# esquemacamisetawifi.net
KiCad netlist of a schematic drawn in EAGLE
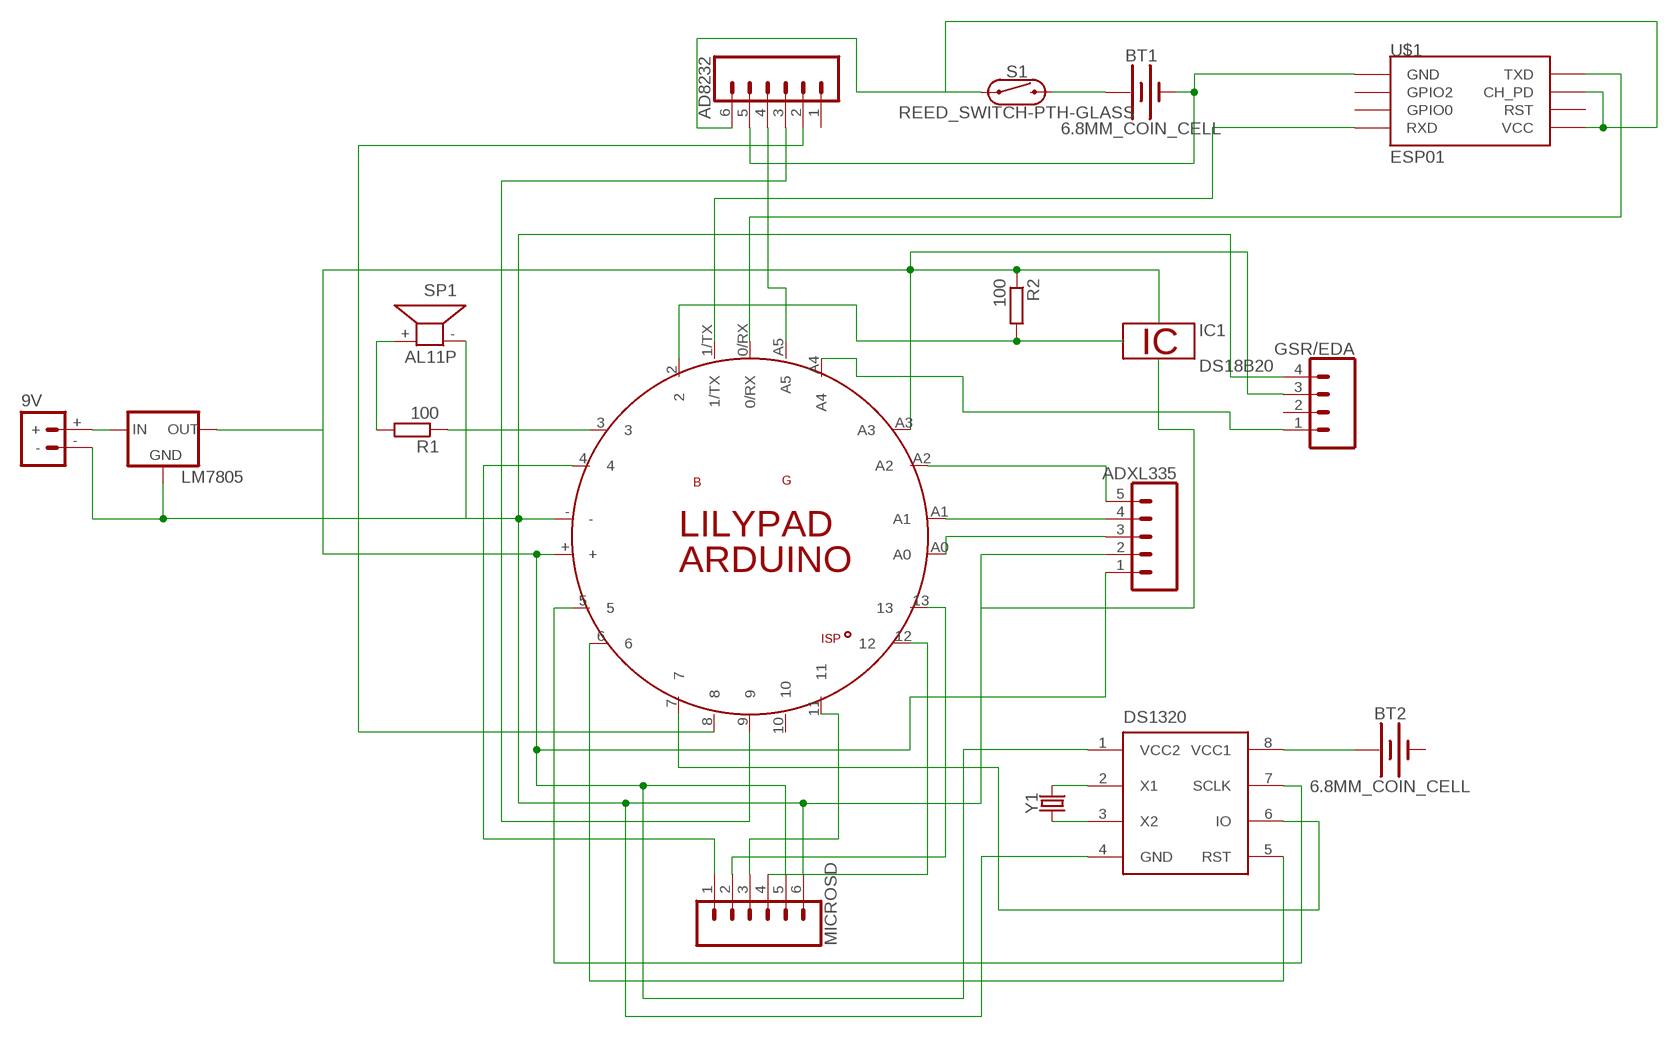
[diagram p0: schematic, sheet 1]

(export (version "E")
  (design (tool "Eeschema 10.0.6"))
  (components
    (comp (ref "9V")
      (value "BATTERY_CONN_DEANS")
      (footprint "eagle-import:DEANS")
      (libsource (lib "eagle-import") (part "BATTERY_CONN_DEANS"))
    )
    (comp (ref "AD8232")
      (value "CONN_06FEMALE_LOCK")
      (footprint "eagle-import:1X06_FEMALE_LOCK.010")
      (libsource (lib "eagle-import") (part "CONN_06FEMALE_LOCK"))
    )
    (comp (ref "ADXL335")
      (value "CONN_05")
      (footprint "eagle-import:1X05")
      (libsource (lib "eagle-import") (part "CONN_05"))
    )
    (comp (ref "BT1")
      (value "6.8MM_COIN_CELL")
      (footprint "eagle-import:BATTCON-6.8MM")
      (libsource (lib "eagle-import") (part "BATTERY-6.8MM_SMD"))
    )
    (comp (ref "BT2")
      (value "6.8MM_COIN_CELL")
      (footprint "eagle-import:BATTCON-6.8MM")
      (libsource (lib "eagle-import") (part "BATTERY-6.8MM_SMD"))
    )
    (comp (ref "DS1320")
      (value "DS1302")
      (footprint "eagle-import:PDIP8")
      (libsource (lib "eagle-import") (part "DS1302"))
    )
    (comp (ref "GSR/EDA")
      (value "CONN_04JST-PTH")
      (footprint "eagle-import:JST-4-PTH")
      (libsource (lib "eagle-import") (part "CONN_04JST-PTH"))
    )
    (comp (ref "IC1")
      (value "DS18B20")
      (footprint "eagle-import:TO92-")
      (libsource (lib "eagle-import") (part "DS18B20"))
    )
    (comp (ref "LM7805")
      (value "V_REG_78XX-TO-220")
      (footprint "eagle-import:TO-220-ALT")
      (libsource (lib "eagle-import") (part "V_REG_78XX-TO-220"))
    )
    (comp (ref "MICROSD")
      (value "CONN_06FEMALE_LOCK")
      (footprint "eagle-import:1X06_FEMALE_LOCK.010")
      (libsource (lib "eagle-import") (part "CONN_06FEMALE_LOCK"))
    )
    (comp (ref "PCB1")
      (value "ARDUINO_LILYPAD")
      (footprint "eagle-import:ARDUINO_LILYPAD")
      (libsource (lib "eagle-import") (part "ARDUINO_LILYPAD"))
    )
    (comp (ref "R1")
      (value "100")
      (footprint "eagle-import:0309_12")
      (libsource (lib "eagle-import") (part "R-EU_0309/12"))
    )
    (comp (ref "R2")
      (value "100")
      (footprint "eagle-import:0309_12")
      (libsource (lib "eagle-import") (part "R-EU_0309/12"))
    )
    (comp (ref "S1")
      (value "REED_SWITCH-PTH-GLASS")
      (footprint "eagle-import:REED_SWITCH_GLASS")
      (libsource (lib "eagle-import") (part "REED_SWITCH-PTH-GLASS"))
    )
    (comp (ref "SP1")
      (value "AL11P")
      (footprint "eagle-import:AL11P")
      (libsource (lib "eagle-import") (part "AL11P"))
    )
    (comp (ref "U$1")
      (value "ESP01")
      (footprint "eagle-import:ESP01")
      (libsource (lib "eagle-import") (part "ESP01"))
    )
    (comp (ref "Y1")
      (value "CRYSTALPTH-2X6")
      (footprint "eagle-import:CRYSTAL-PTH-2X6-CYL")
      (libsource (lib "eagle-import") (part "CRYSTALPTH-2X6"))
    )
  )
  (nets
    (net (code "1") (name "/-") (class "Default")
      (node (ref "BT2") (pin "-") (pinfunction "-_-") (pintype "power_in"))
    )
    (net (code "2") (name "Net-(9V-Pad+)") (class "Default")
      (node (ref "9V") (pin "+") (pinfunction "+_+") (pintype "passive"))
      (node (ref "LM7805") (pin "IN") (pinfunction "IN_IN") (pintype "input"))
    )
    (net (code "3") (name "Net-(AD8232-Pad2)") (class "Default")
      (node (ref "AD8232") (pin "2") (pinfunction "2_2") (pintype "passive"))
      (node (ref "PCB1") (pin "8") (pinfunction "8_8") (pintype "bidirectional"))
    )
    (net (code "4") (name "Net-(AD8232-Pad3)") (class "Default")
      (node (ref "AD8232") (pin "3") (pinfunction "3_3") (pintype "passive"))
      (node (ref "PCB1") (pin "9") (pinfunction "9_9") (pintype "bidirectional"))
    )
    (net (code "5") (name "Net-(AD8232-Pad4)") (class "Default")
      (node (ref "AD8232") (pin "4") (pinfunction "4_4") (pintype "passive"))
      (node (ref "PCB1") (pin "A5") (pinfunction "A5_A5") (pintype "bidirectional"))
    )
    (net (code "6") (name "Net-(AD8232-Pad5)") (class "Default")
      (node (ref "AD8232") (pin "5") (pinfunction "5_5") (pintype "passive"))
      (node (ref "BT1") (pin "-") (pinfunction "-_-") (pintype "power_in"))
      (node (ref "U$1") (pin "GND") (pinfunction "GND_GND") (pintype "bidirectional"))
    )
    (net (code "7") (name "Net-(ADXL335-Pad3)") (class "Default")
      (node (ref "ADXL335") (pin "3") (pinfunction "3_3") (pintype "passive"))
      (node (ref "PCB1") (pin "A0") (pinfunction "A0_A0") (pintype "bidirectional"))
    )
    (net (code "8") (name "Net-(ADXL335-Pad4)") (class "Default")
      (node (ref "ADXL335") (pin "4") (pinfunction "4_4") (pintype "passive"))
      (node (ref "PCB1") (pin "A1") (pinfunction "A1_A1") (pintype "bidirectional"))
    )
    (net (code "9") (name "Net-(ADXL335-Pad5)") (class "Default")
      (node (ref "ADXL335") (pin "5") (pinfunction "5_5") (pintype "passive"))
      (node (ref "PCB1") (pin "A2") (pinfunction "A2_A2") (pintype "bidirectional"))
    )
    (net (code "10") (name "Net-(DS1320-GND)") (class "Default")
      (node (ref "9V") (pin "-") (pinfunction "-_-") (pintype "passive"))
      (node (ref "ADXL335") (pin "2") (pinfunction "2_2") (pintype "passive"))
      (node (ref "DS1320") (pin "4") (pinfunction "GND_4") (pintype "power_in"))
      (node (ref "GSR/EDA") (pin "4") (pinfunction "4_4") (pintype "passive"))
      (node (ref "LM7805") (pin "GND") (pinfunction "GND_GND") (pintype "input"))
      (node (ref "MICROSD") (pin "6") (pinfunction "6_6") (pintype "passive"))
      (node (ref "PCB1") (pin "-") (pinfunction "-_-") (pintype "bidirectional"))
      (node (ref "SP1") (pin "-") (pinfunction "1_-") (pintype "passive"))
    )
    (net (code "11") (name "Net-(DS1320-IO)") (class "Default")
      (node (ref "DS1320") (pin "6") (pinfunction "IO_6") (pintype "bidirectional"))
      (node (ref "PCB1") (pin "7") (pinfunction "7_7") (pintype "bidirectional"))
    )
    (net (code "12") (name "Net-(DS1320-RST)") (class "Default")
      (node (ref "DS1320") (pin "5") (pinfunction "RST_5") (pintype "input"))
      (node (ref "PCB1") (pin "6") (pinfunction "6_6") (pintype "bidirectional"))
    )
    (net (code "13") (name "Net-(DS1320-SCLK)") (class "Default")
      (node (ref "DS1320") (pin "7") (pinfunction "SCLK_7") (pintype "input"))
      (node (ref "PCB1") (pin "5") (pinfunction "5_5") (pintype "bidirectional"))
    )
    (net (code "14") (name "Net-(DS1320-VCC1)") (class "Default")
      (node (ref "BT2") (pin "+") (pinfunction "+_+") (pintype "power_in"))
      (node (ref "DS1320") (pin "8") (pinfunction "VCC1_8") (pintype "power_in"))
    )
    (net (code "15") (name "Net-(DS1320-VCC2)") (class "Default")
      (node (ref "ADXL335") (pin "1") (pinfunction "1_1") (pintype "passive"))
      (node (ref "DS1320") (pin "1") (pinfunction "VCC2_1") (pintype "power_in"))
      (node (ref "GSR/EDA") (pin "3") (pinfunction "3_3") (pintype "passive"))
      (node (ref "MICROSD") (pin "5") (pinfunction "5_5") (pintype "passive"))
      (node (ref "PCB1") (pin "+") (pinfunction "+_+") (pintype "bidirectional"))
      (node (ref "PCB1") (pin "A3") (pinfunction "A3_A3") (pintype "bidirectional"))
      (node (ref "R2") (pin "1") (pinfunction "1_1") (pintype "passive"))
    )
    (net (code "16") (name "Net-(DS1320-X1)") (class "Default")
      (node (ref "DS1320") (pin "2") (pinfunction "X1_2") (pintype "bidirectional"))
      (node (ref "Y1") (pin "2") (pinfunction "2_2") (pintype "passive"))
    )
    (net (code "17") (name "Net-(DS1320-X2)") (class "Default")
      (node (ref "DS1320") (pin "3") (pinfunction "X2_3") (pintype "bidirectional"))
      (node (ref "Y1") (pin "1") (pinfunction "1_1") (pintype "passive"))
    )
    (net (code "18") (name "Net-(GSR/EDA-Pad1)") (class "Default")
      (node (ref "GSR/EDA") (pin "1") (pinfunction "1_1") (pintype "passive"))
      (node (ref "PCB1") (pin "A4") (pinfunction "A4_A4") (pintype "bidirectional"))
    )
    (net (code "19") (name "Net-(MICROSD-Pad1)") (class "Default")
      (node (ref "MICROSD") (pin "1") (pinfunction "1_1") (pintype "passive"))
      (node (ref "PCB1") (pin "4") (pinfunction "4_4") (pintype "bidirectional"))
    )
    (net (code "20") (name "Net-(MICROSD-Pad2)") (class "Default")
      (node (ref "MICROSD") (pin "2") (pinfunction "2_2") (pintype "passive"))
      (node (ref "PCB1") (pin "13") (pinfunction "13_13") (pintype "bidirectional"))
    )
    (net (code "21") (name "Net-(MICROSD-Pad3)") (class "Default")
      (node (ref "MICROSD") (pin "3") (pinfunction "3_3") (pintype "passive"))
      (node (ref "PCB1") (pin "11") (pinfunction "11_11") (pintype "bidirectional"))
    )
    (net (code "22") (name "Net-(MICROSD-Pad4)") (class "Default")
      (node (ref "MICROSD") (pin "4") (pinfunction "4_4") (pintype "passive"))
      (node (ref "PCB1") (pin "12") (pinfunction "12_12") (pintype "bidirectional"))
    )
    (net (code "23") (name "Net-(PCB1-Pad2)") (class "Default")
      (node (ref "PCB1") (pin "2") (pinfunction "2_2") (pintype "bidirectional"))
      (node (ref "R2") (pin "2") (pinfunction "2_2") (pintype "passive"))
    )
    (net (code "24") (name "Net-(PCB1-Pad3)") (class "Default")
      (node (ref "PCB1") (pin "3") (pinfunction "3_3") (pintype "bidirectional"))
      (node (ref "R1") (pin "1") (pinfunction "1_1") (pintype "passive"))
    )
    (net (code "25") (name "Net-(S1-1)") (class "Default")
      (node (ref "AD8232") (pin "6") (pinfunction "6_6") (pintype "passive"))
      (node (ref "S1") (pin "P$1") (pinfunction "1_P$1") (pintype "passive"))
      (node (ref "U$1") (pin "CH_PD") (pinfunction "CH_PD_CH_PD") (pintype "bidirectional"))
      (node (ref "U$1") (pin "VCC") (pinfunction "VCC_VCC") (pintype "bidirectional"))
    )
    (net (code "26") (name "Net-(S1-2)") (class "Default")
      (node (ref "BT1") (pin "+") (pinfunction "+_+") (pintype "power_in"))
      (node (ref "S1") (pin "P$2") (pinfunction "2_P$2") (pintype "passive"))
    )
    (net (code "27") (name "Net-(SP1-2)") (class "Default")
      (node (ref "R1") (pin "2") (pinfunction "2_2") (pintype "passive"))
      (node (ref "SP1") (pin "+") (pinfunction "2_+") (pintype "passive"))
    )
    (net (code "28") (name "Net-(U$1-RXD)") (class "Default")
      (node (ref "PCB1") (pin "1/TX") (pinfunction "1/TX_1/TX") (pintype "bidirectional"))
      (node (ref "U$1") (pin "RX") (pinfunction "RXD_RX") (pintype "bidirectional"))
    )
    (net (code "29") (name "Net-(U$1-TXD)") (class "Default")
      (node (ref "PCB1") (pin "0/RX") (pinfunction "0/RX_0/RX") (pintype "bidirectional"))
      (node (ref "U$1") (pin "TX") (pinfunction "TXD_TX") (pintype "bidirectional"))
    )
    (net (code "30") (name "unconnected-(AD8232-Pad1)") (class "Default")
      (node (ref "AD8232") (pin "1") (pinfunction "1_1") (pintype "passive"))
    )
    (net (code "31") (name "unconnected-(GSR/EDA-Pad2)") (class "Default")
      (node (ref "GSR/EDA") (pin "2") (pinfunction "2_2") (pintype "passive"))
    )
    (net (code "32") (name "unconnected-(LM7805-PadOUT)") (class "Default")
      (node (ref "LM7805") (pin "OUT") (pinfunction "OUT_OUT") (pintype "passive"))
    )
    (net (code "33") (name "unconnected-(PCB1-GND-PadGND_)") (class "Default")
      (node (ref "PCB1") (pin "GND_") (pinfunction "GND_GND_") (pintype "bidirectional"))
    )
    (net (code "34") (name "unconnected-(PCB1-Pad10)") (class "Default")
      (node (ref "PCB1") (pin "10") (pinfunction "10_10") (pintype "bidirectional"))
    )
    (net (code "35") (name "unconnected-(PCB1-PadDTR)") (class "Default")
      (node (ref "PCB1") (pin "DTR") (pinfunction "DTR_DTR") (pintype "bidirectional"))
    )
    (net (code "36") (name "unconnected-(PCB1-PadGND.)") (class "Default")
      (node (ref "PCB1") (pin "GND.") (pinfunction "GND._GND.") (pintype "bidirectional"))
    )
    (net (code "37") (name "unconnected-(PCB1-PadGND..)") (class "Default")
      (node (ref "PCB1") (pin "GND..") (pinfunction "GND.._GND..") (pintype "bidirectional"))
    )
    (net (code "38") (name "unconnected-(PCB1-PadMISO)") (class "Default")
      (node (ref "PCB1") (pin "MISO") (pinfunction "MISO_MISO") (pintype "bidirectional"))
    )
    (net (code "39") (name "unconnected-(PCB1-PadMOSI)") (class "Default")
      (node (ref "PCB1") (pin "MOSI") (pinfunction "MOSI_MOSI") (pintype "bidirectional"))
    )
    (net (code "40") (name "unconnected-(PCB1-PadRXI)") (class "Default")
      (node (ref "PCB1") (pin "RXI") (pinfunction "RXI_RXI") (pintype "bidirectional"))
    )
    (net (code "41") (name "unconnected-(PCB1-PadSCK)") (class "Default")
      (node (ref "PCB1") (pin "SCK") (pinfunction "SCK_SCK") (pintype "bidirectional"))
    )
    (net (code "42") (name "unconnected-(PCB1-PadTXO)") (class "Default")
      (node (ref "PCB1") (pin "TXO") (pinfunction "TXO_TXO") (pintype "bidirectional"))
    )
    (net (code "43") (name "unconnected-(PCB1-PadVCC.)") (class "Default")
      (node (ref "PCB1") (pin "VCC.") (pinfunction "VCC._VCC.") (pintype "bidirectional"))
    )
    (net (code "44") (name "unconnected-(PCB1-RST-PadRESET..)") (class "Default")
      (node (ref "PCB1") (pin "RESET..") (pinfunction "RST_RESET..") (pintype "bidirectional"))
    )
    (net (code "45") (name "unconnected-(PCB1-VCC-Pad5V.)") (class "Default")
      (node (ref "PCB1") (pin "5V.") (pinfunction "VCC_5V.") (pintype "bidirectional"))
    )
    (net (code "46") (name "unconnected-(U$1-PadGPIO0)") (class "Default")
      (node (ref "U$1") (pin "GPIO0") (pinfunction "GPIO0_GPIO0") (pintype "bidirectional"))
    )
    (net (code "47") (name "unconnected-(U$1-PadGPIO2)") (class "Default")
      (node (ref "U$1") (pin "GPIO2") (pinfunction "GPIO2_GPIO2") (pintype "bidirectional"))
    )
    (net (code "48") (name "unconnected-(U$1-PadRST)") (class "Default")
      (node (ref "U$1") (pin "RST") (pinfunction "RST_RST") (pintype "bidirectional"))
    )
  )
)
